# V1_01.net
KiCad netlist of a schematic drawn in EAGLE
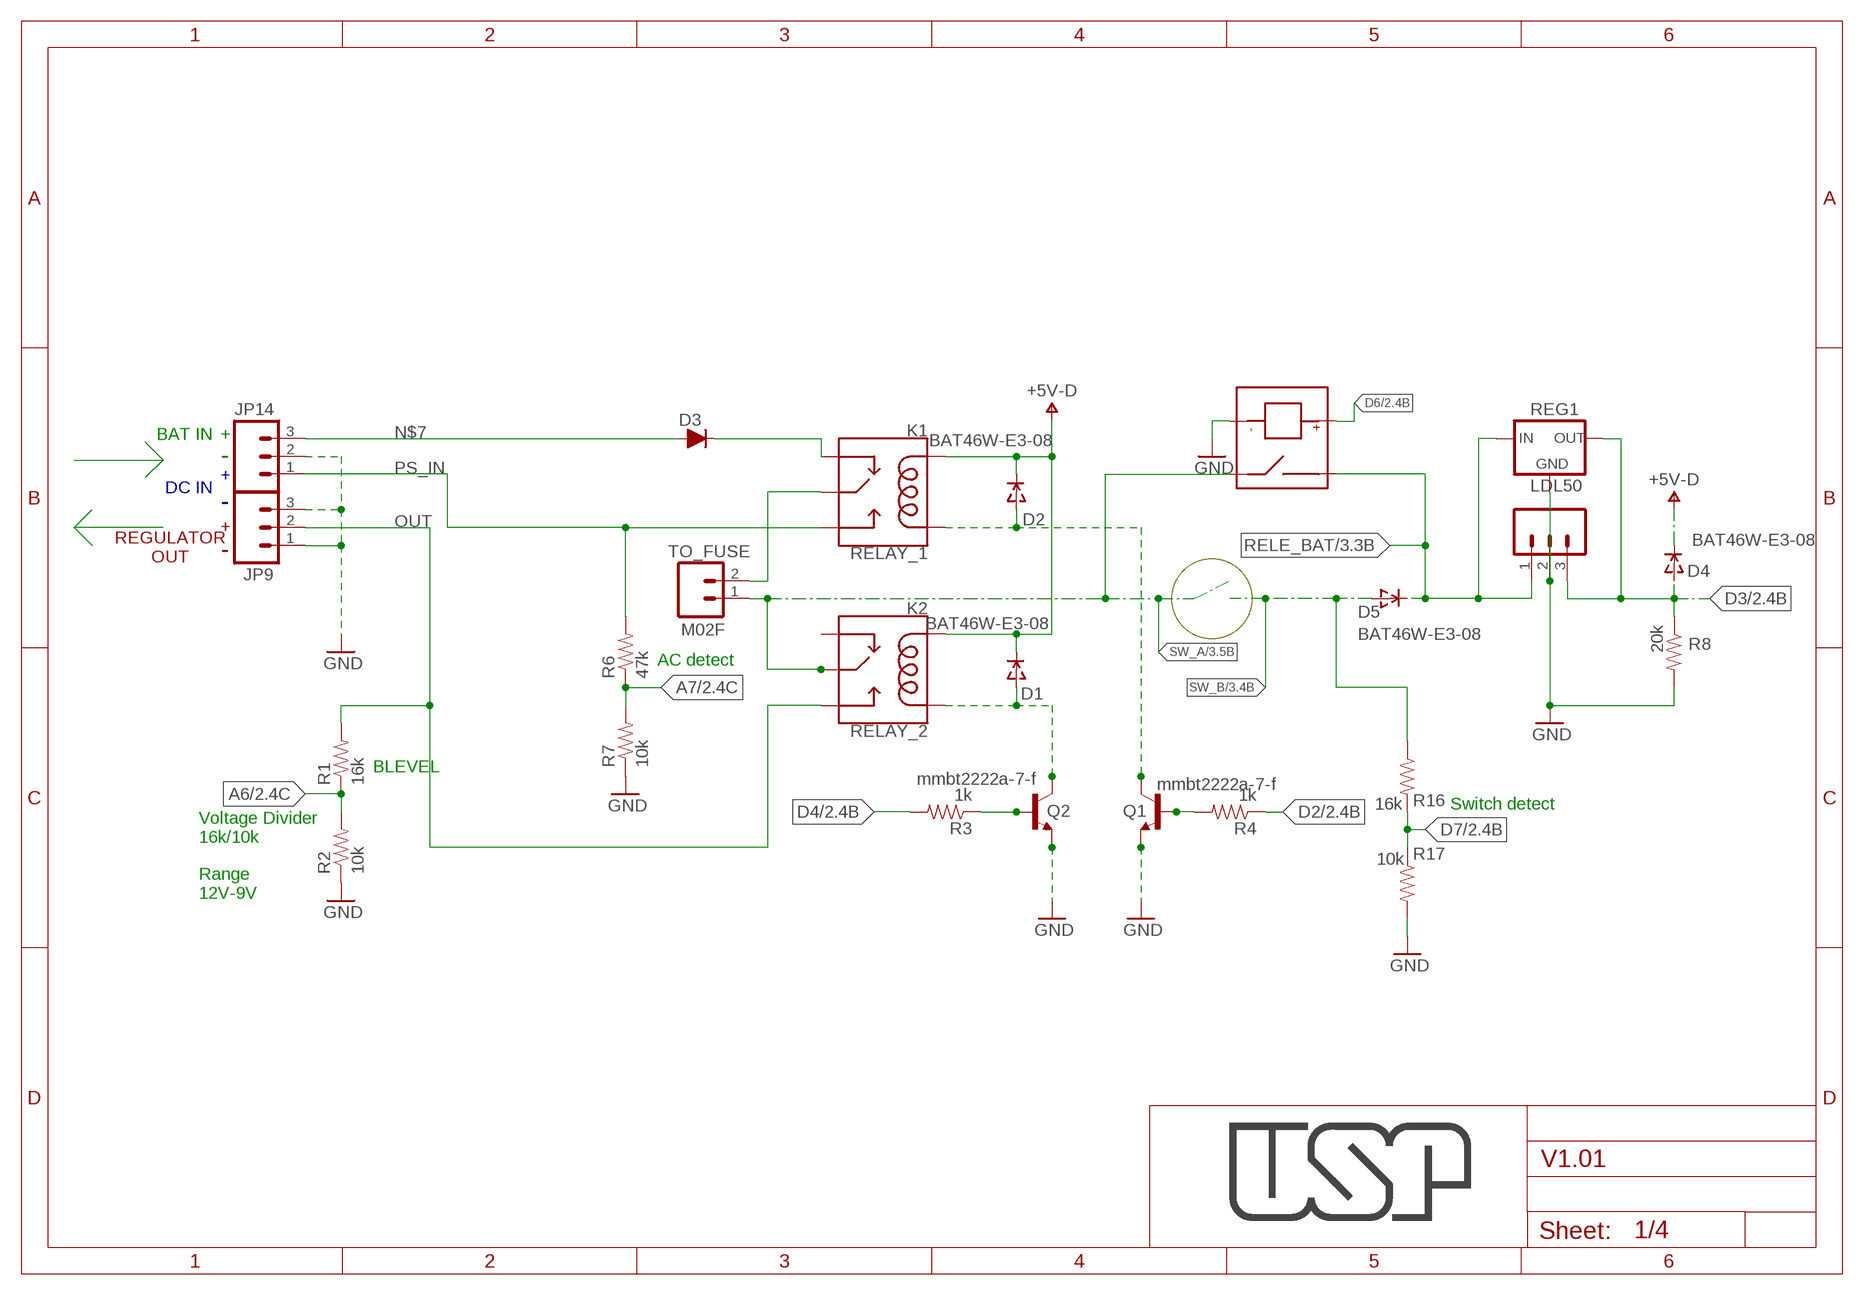
[diagram p0: schematic, sheet 1]
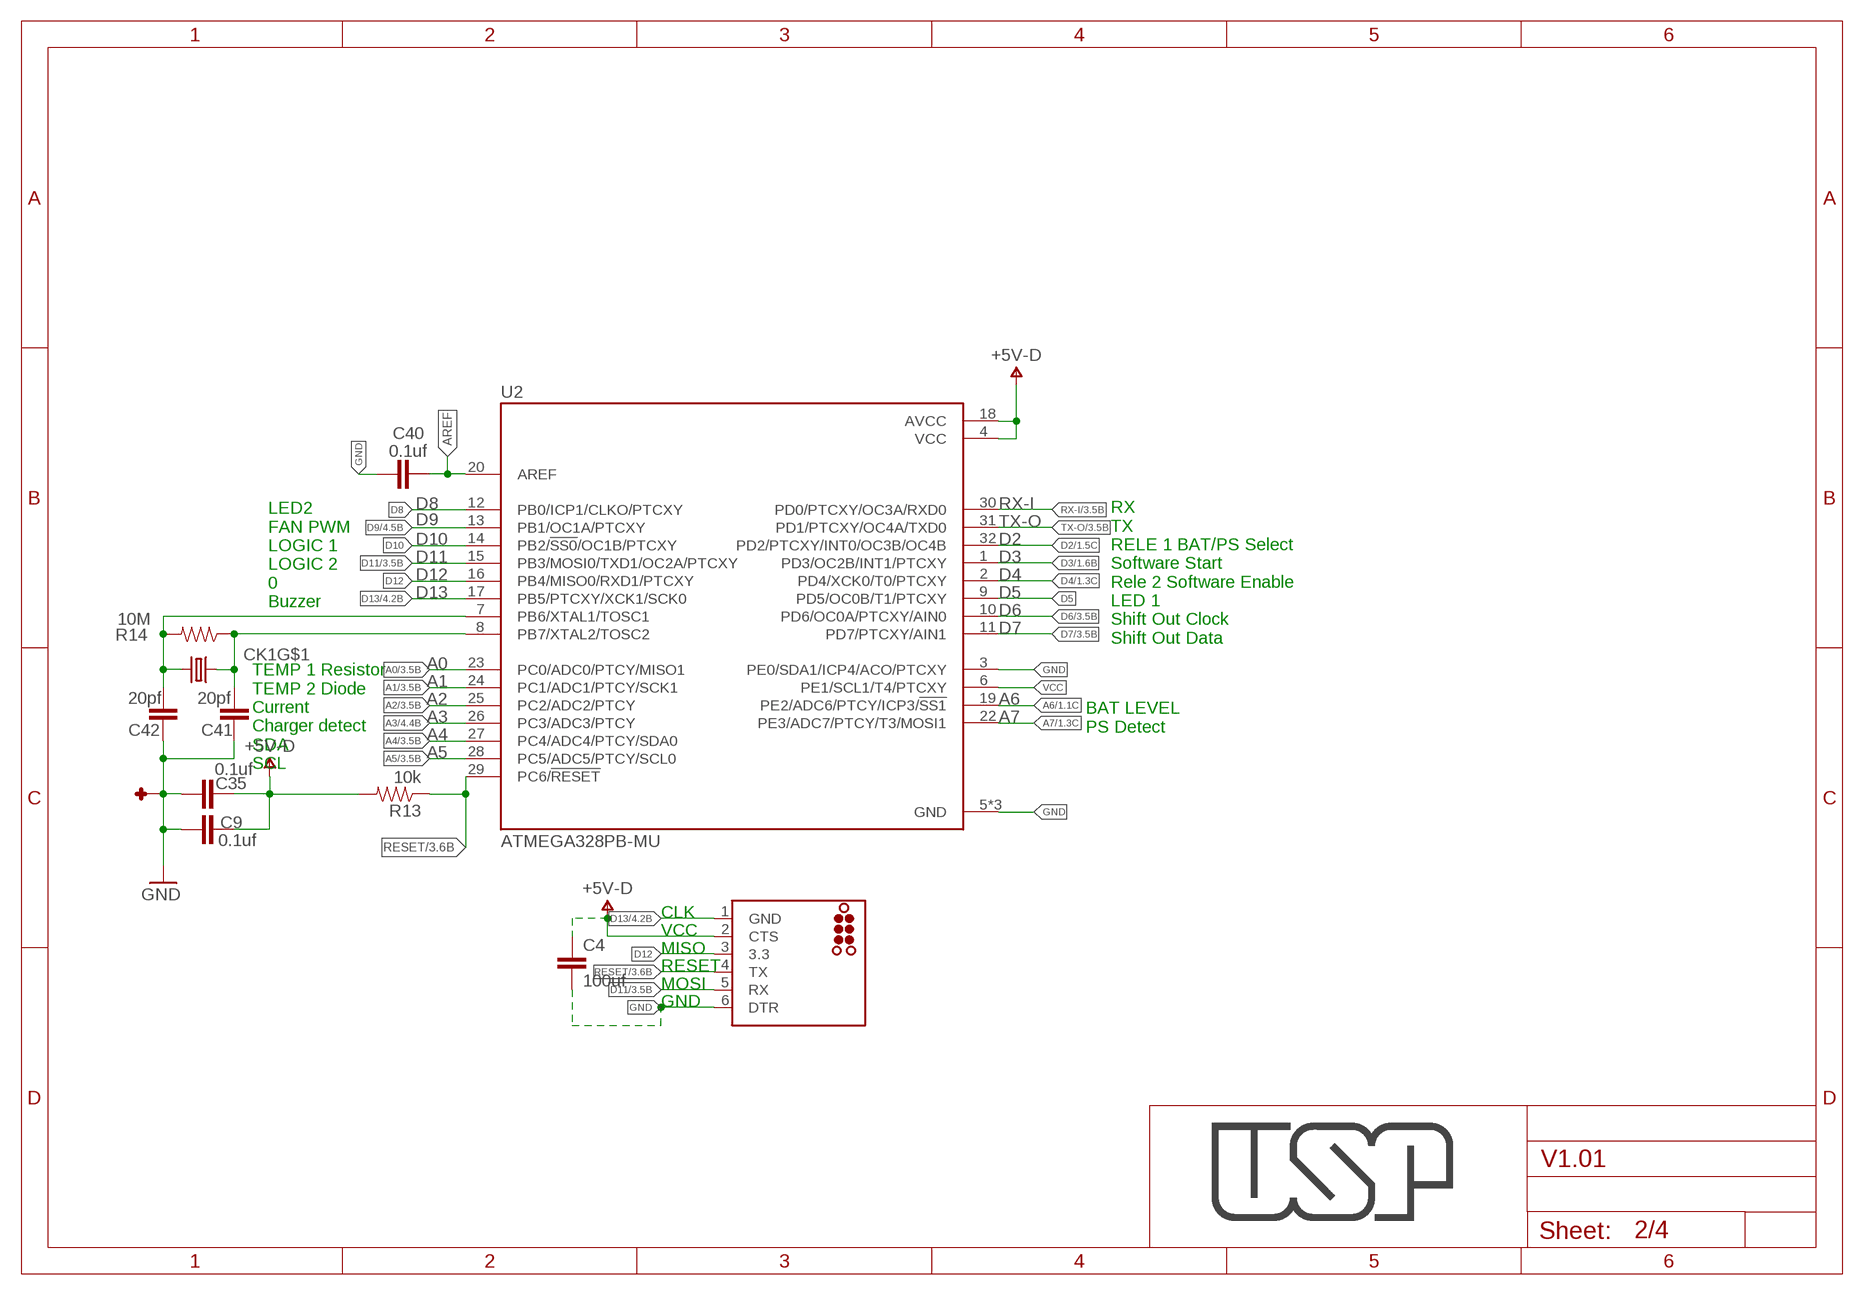
[diagram p1: schematic, sheet 2]
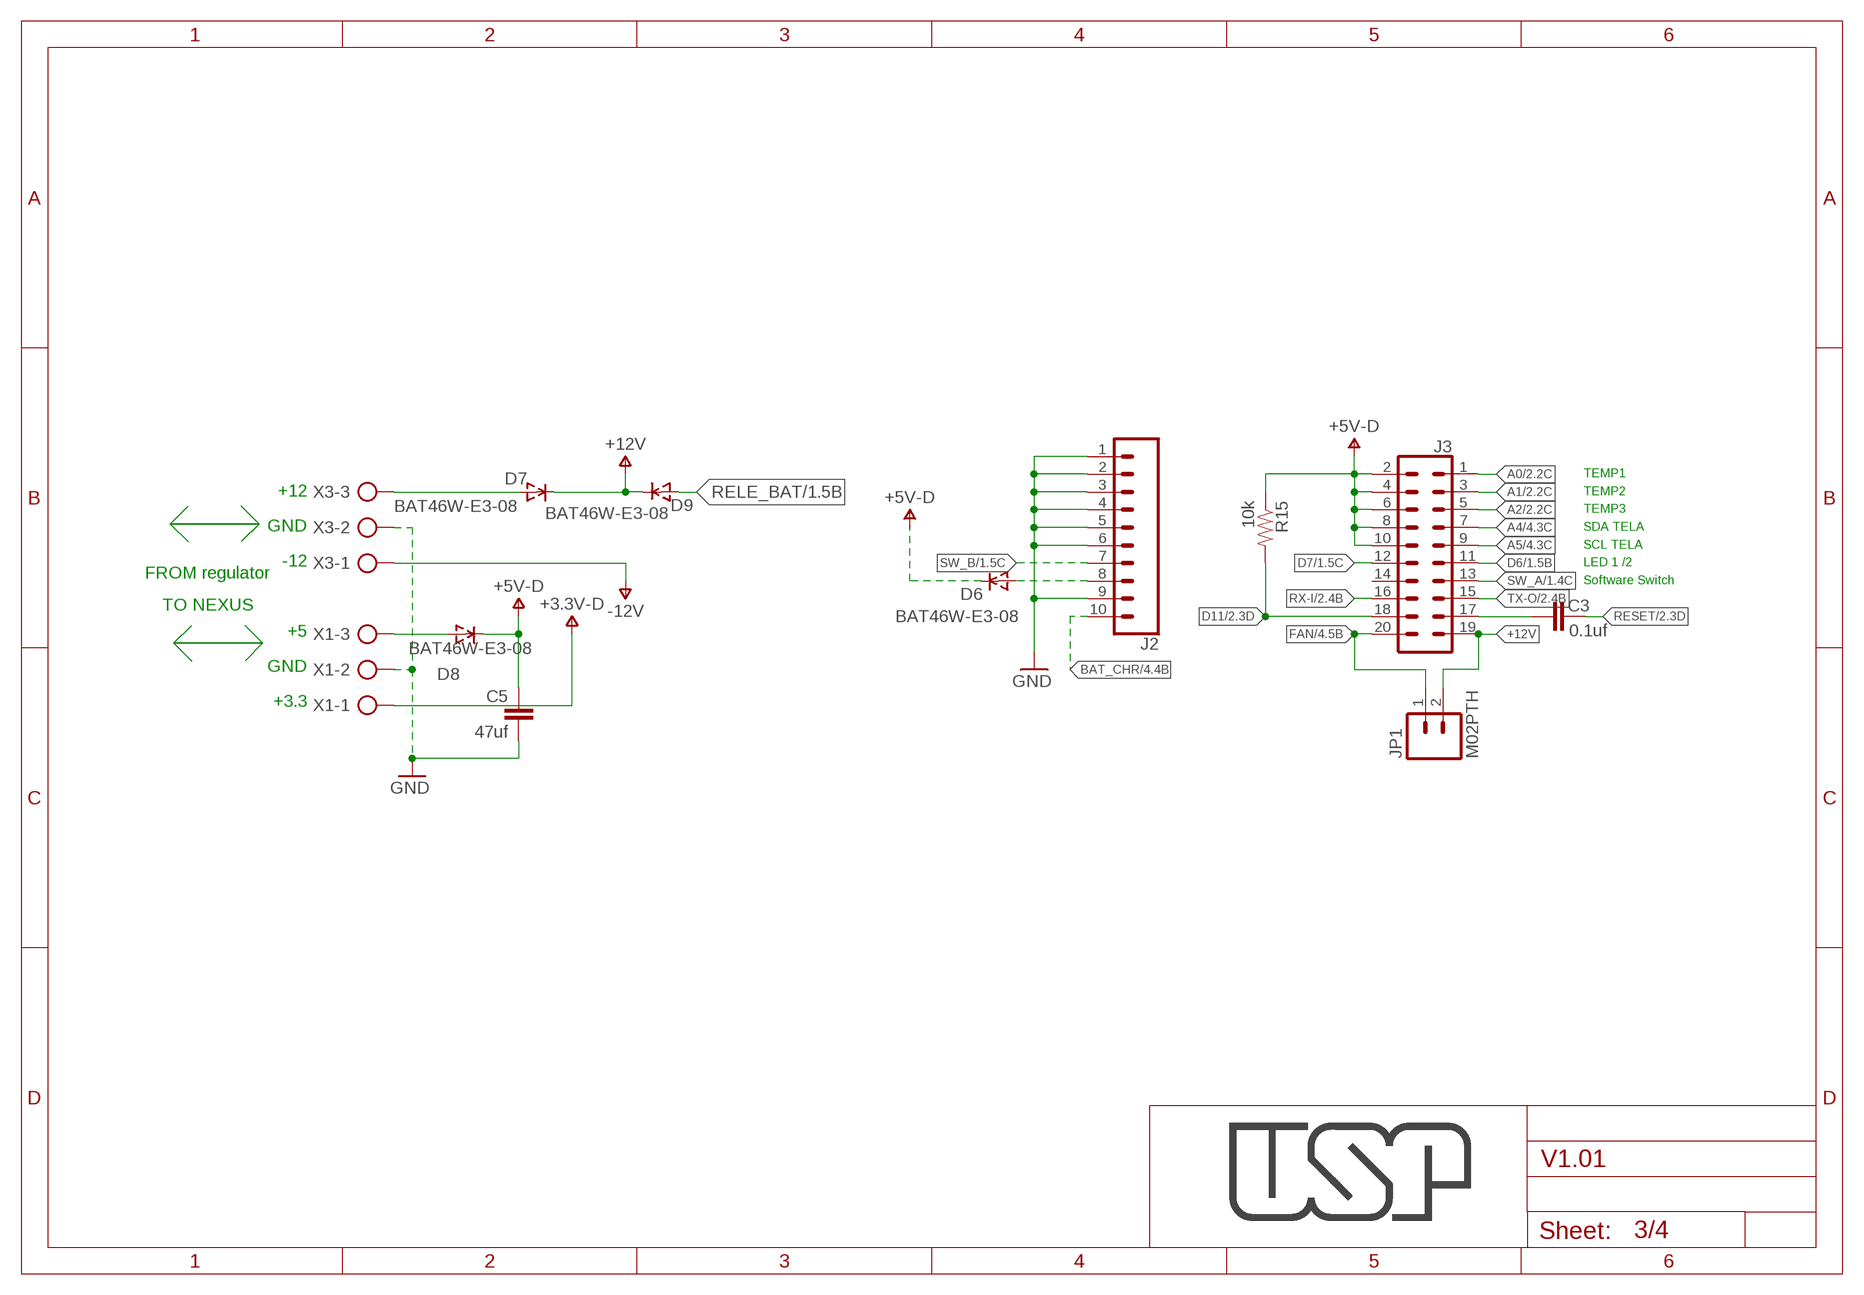
[diagram p2: schematic, sheet 3]
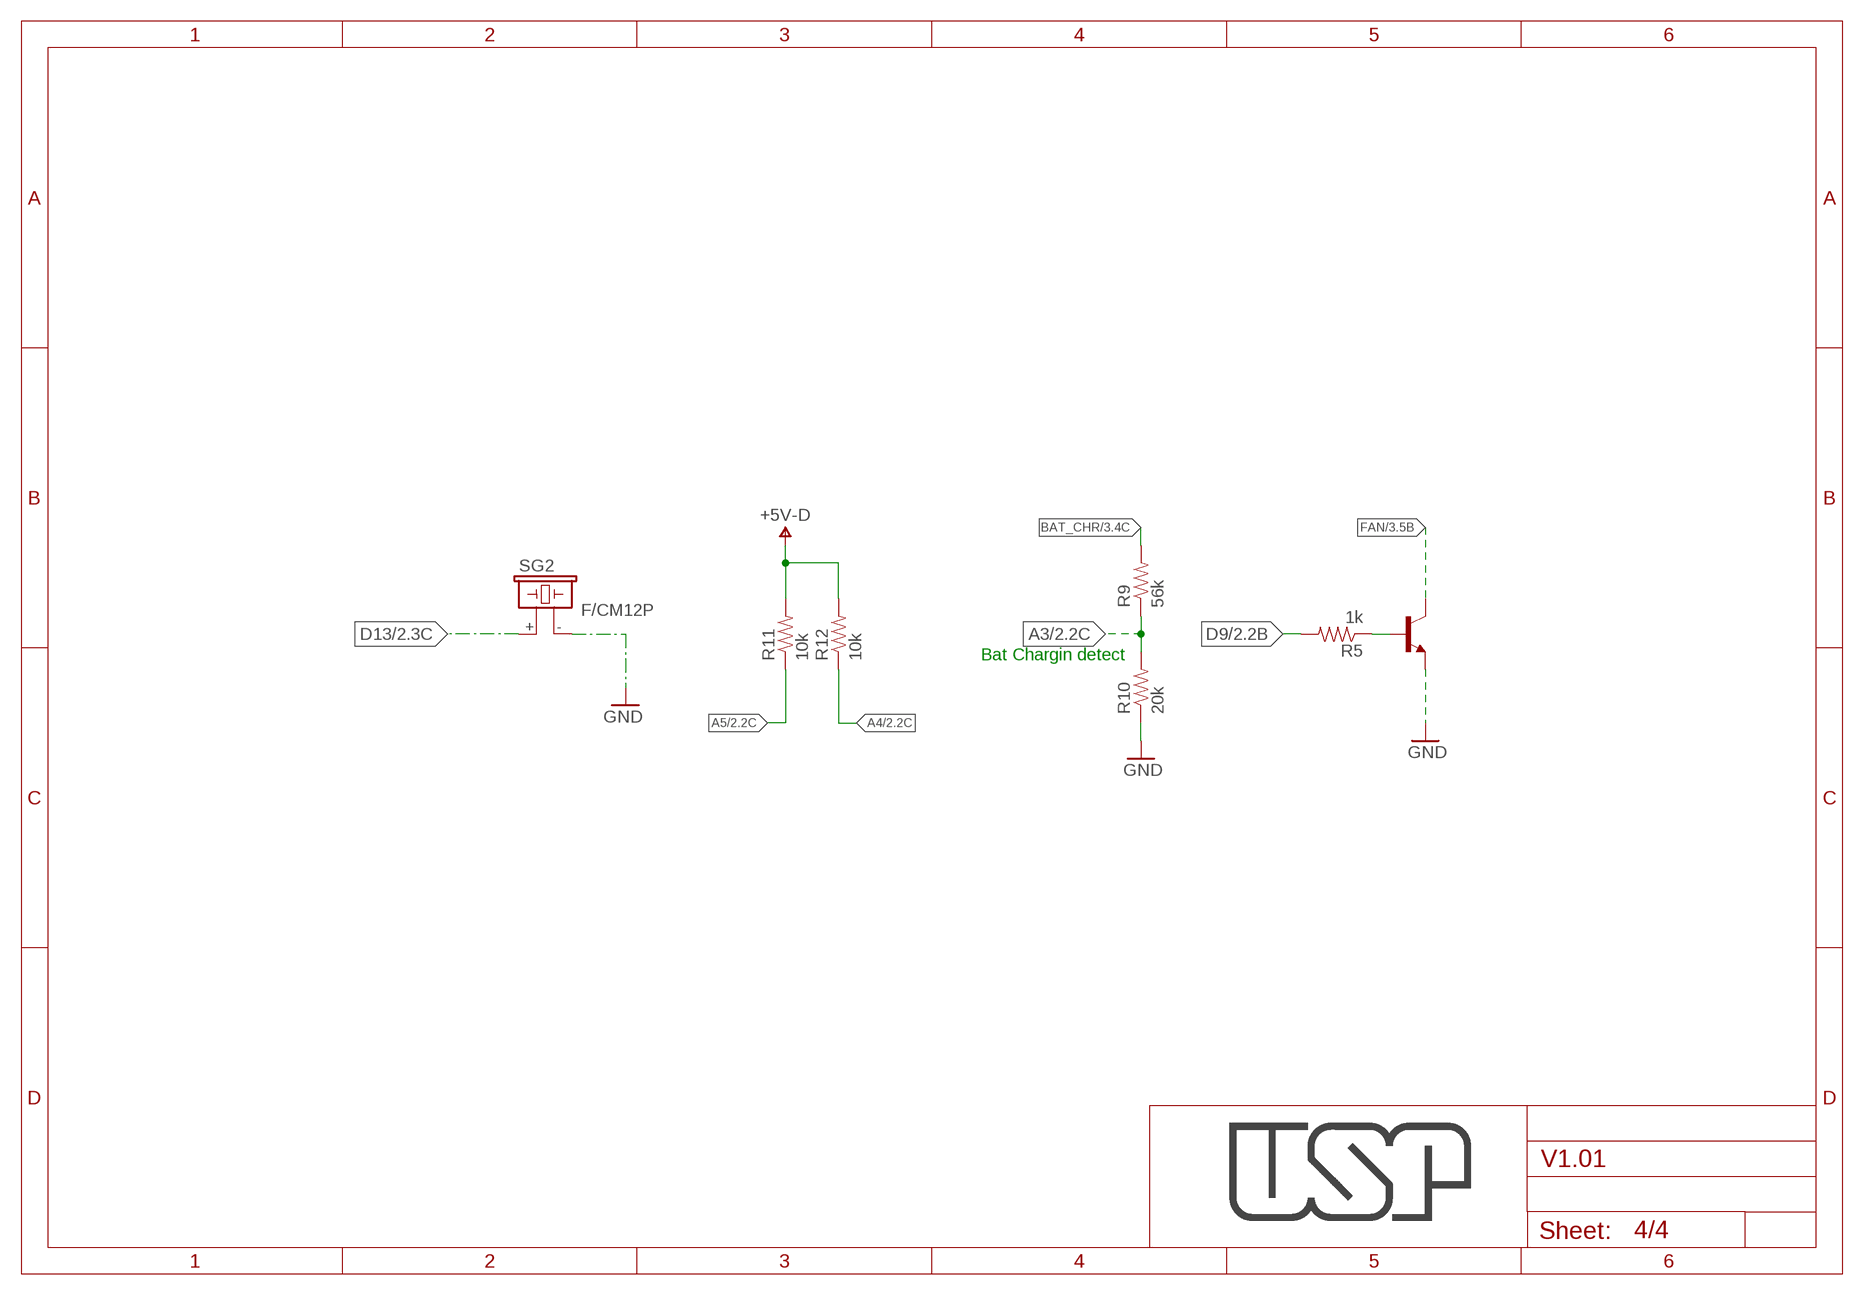
[diagram p3: schematic, sheet 4]

(export (version "E")
  (design (tool "Eeschema 10.0.6"))
  (components
    (comp (ref "C3")
      (value "0.1uf")
      (footprint "eagle-import:0402")
      (libsource (lib "eagle-import") (part "CAPACITOR-KIT-1VISHAY"))
    )
    (comp (ref "C5")
      (value "47uf")
      (footprint "eagle-import:1206")
      (libsource (lib "eagle-import") (part "CAPACITOR-KIT-11206"))
    )
    (comp (ref "D6")
      (value "BAT46W-E3-08")
      (footprint "eagle-import:SOD-123")
      (libsource (lib "eagle-import") (part "DIODE_1SOD-123"))
    )
    (comp (ref "D7")
      (value "BAT46W-E3-08")
      (footprint "eagle-import:SOD-123")
      (libsource (lib "eagle-import") (part "DIODE_1SOD-123"))
    )
    (comp (ref "D8")
      (value "BAT46W-E3-08")
      (footprint "eagle-import:SOD-123")
      (libsource (lib "eagle-import") (part "DIODE_1SOD-123"))
    )
    (comp (ref "D9")
      (value "BAT46W-E3-08")
      (footprint "eagle-import:SOD-123")
      (libsource (lib "eagle-import") (part "DIODE_1SOD-123"))
    )
    (comp (ref "J2")
      (value "CONN_10\"")
      (footprint "eagle-import:1X10")
      (libsource (lib "eagle-import") (part "CONN_10{dblquote}"))
    )
    (comp (ref "J3")
      (value "CONN_10X2")
      (footprint "eagle-import:2X10")
      (libsource (lib "eagle-import") (part "CONN_10X2"))
    )
    (comp (ref "JP1")
      (value "M02PTH")
      (footprint "eagle-import:1X02")
      (libsource (lib "eagle-import") (part "M02PTH"))
    )
    (comp (ref "R15")
      (value "10k")
      (footprint "eagle-import:0402")
      (libsource (lib "eagle-import") (part "RESISTORVISHAY"))
    )
    (comp (ref "X1")
      (value "AK500/3-H")
      (footprint "eagle-import:AK500_3-H")
      (libsource (lib "eagle-import") (part "AK500/3-H"))
    )
    (comp (ref "X3")
      (value "AK500/3-H")
      (footprint "eagle-import:AK500_3-H")
      (libsource (lib "eagle-import") (part "AK500/3-H"))
    )
    (comp (ref "C4")
      (value "100uf")
      (footprint "eagle-import:1206")
      (libsource (lib "eagle-import") (part "CAPACITOR-KIT-11206"))
    )
    (comp (ref "C9")
      (value "0.1uf")
      (footprint "eagle-import:0402")
      (libsource (lib "eagle-import") (part "CAPACITOR-KIT-1VISHAY"))
    )
    (comp (ref "C35")
      (value "0.1uf")
      (footprint "eagle-import:0402")
      (libsource (lib "eagle-import") (part "CAPACITOR-KIT-1VISHAY"))
    )
    (comp (ref "C40")
      (value "0.1uf")
      (footprint "eagle-import:0402")
      (libsource (lib "eagle-import") (part "CAPACITOR-KIT-1VISHAY"))
    )
    (comp (ref "C41")
      (value "20pf")
      (footprint "eagle-import:0402")
      (libsource (lib "eagle-import") (part "CAPACITOR-KIT-1VISHAY"))
    )
    (comp (ref "C42")
      (value "20pf")
      (footprint "eagle-import:0402")
      (libsource (lib "eagle-import") (part "CAPACITOR-KIT-1VISHAY"))
    )
    (comp (ref "CK1")
      (value "FA-238 16.0000MB-C3")
      (footprint "eagle-import:4-SMD@1")
      (libsource (lib "eagle-import") (part "CRYSTAL-4PAD"))
    )
    (comp (ref "J10")
      (value "DNP")
      (footprint "eagle-import:TC2030-MCP-NL")
      (libsource (lib "eagle-import") (part "FTDI-POGO-MCP-NL"))
    )
    (comp (ref "R13")
      (value "10k")
      (footprint "eagle-import:0402")
      (libsource (lib "eagle-import") (part "RESISTORVISHAY"))
    )
    (comp (ref "R14")
      (value "10M")
      (footprint "eagle-import:0402")
      (libsource (lib "eagle-import") (part "RESISTORVISHAY"))
    )
    (comp (ref "U2")
      (value "ATMEGA328PB-MU")
      (footprint "eagle-import:QFN50P500X500X90-33N")
      (fields (field (name "MF") "Microchip"))
      (libsource (lib "eagle-import") (part "ATMEGA328PB-MU"))
    )
    (comp (ref "Q5")
      (value "TRANSISTOR-NPN-BC337")
      (footprint "eagle-import:BC337")
      (libsource (lib "eagle-import") (part "TRANSISTOR-NPN-BC337"))
    )
    (comp (ref "R5")
      (value "1k")
      (footprint "eagle-import:0402")
      (libsource (lib "eagle-import") (part "RESISTORVISHAY"))
    )
    (comp (ref "R9")
      (value "56k")
      (footprint "eagle-import:0402")
      (libsource (lib "eagle-import") (part "RESISTORVISHAY"))
    )
    (comp (ref "R10")
      (value "20k")
      (footprint "eagle-import:0402")
      (libsource (lib "eagle-import") (part "RESISTORVISHAY"))
    )
    (comp (ref "R11")
      (value "10k")
      (footprint "eagle-import:0402")
      (libsource (lib "eagle-import") (part "RESISTORVISHAY"))
    )
    (comp (ref "R12")
      (value "10k")
      (footprint "eagle-import:0402")
      (libsource (lib "eagle-import") (part "RESISTORVISHAY"))
    )
    (comp (ref "SG2")
      (value "F/CM12P")
      (footprint "eagle-import:F_CM12P")
      (libsource (lib "eagle-import") (part "F/CM12P"))
    )
    (comp (ref "7805")
      (value "M03LOCK")
      (footprint "eagle-import:1X03_LOCK")
      (libsource (lib "eagle-import") (part "M03LOCK"))
    )
    (comp (ref "D1")
      (value "BAT46W-E3-08")
      (footprint "eagle-import:SOD-123")
      (libsource (lib "eagle-import") (part "DIODE_1SOD-123"))
    )
    (comp (ref "D2")
      (value "BAT46W-E3-08")
      (footprint "eagle-import:SOD-123")
      (libsource (lib "eagle-import") (part "DIODE_1SOD-123"))
    )
    (comp (ref "D3")
      (value "DIODEFR")
      (footprint "eagle-import:DIODE1.5A")
      (libsource (lib "eagle-import") (part "DIODEFR"))
    )
    (comp (ref "D4")
      (value "BAT46W-E3-08")
      (footprint "eagle-import:SOD-123")
      (libsource (lib "eagle-import") (part "DIODE_1SOD-123"))
    )
    (comp (ref "D5")
      (value "BAT46W-E3-08")
      (footprint "eagle-import:SOD-123")
      (libsource (lib "eagle-import") (part "DIODE_1SOD-123"))
    )
    (comp (ref "JP9")
      (value "M03")
      (footprint "eagle-import:AK500")
      (libsource (lib "eagle-import") (part "M03"))
    )
    (comp (ref "JP14")
      (value "M03")
      (footprint "eagle-import:AK500")
      (libsource (lib "eagle-import") (part "M03"))
    )
    (comp (ref "K1")
      (value "RELAY_1")
      (footprint "eagle-import:RELAY_G5LE")
      (libsource (lib "eagle-import") (part "RELAY-PACKA"))
    )
    (comp (ref "K2")
      (value "RELAY_2")
      (footprint "eagle-import:RELAY_G5LE")
      (libsource (lib "eagle-import") (part "RELAY-PACKA"))
    )
    (comp (ref "Q1")
      (value "mmbt2222a-7-f")
      (footprint "eagle-import:SOT23-3")
      (libsource (lib "eagle-import") (part "TRANSISTOR_NPNMPSA42"))
    )
    (comp (ref "Q2")
      (value "mmbt2222a-7-f")
      (footprint "eagle-import:SOT23-3")
      (libsource (lib "eagle-import") (part "TRANSISTOR_NPNMPSA42"))
    )
    (comp (ref "Q3")
      (value "TRANSISTOR-NPN-BC337")
      (footprint "eagle-import:BC337")
      (libsource (lib "eagle-import") (part "TRANSISTOR-NPN-BC337"))
    )
    (comp (ref "Q4")
      (value "TRANSISTOR-NPN-BC337")
      (footprint "eagle-import:BC337")
      (libsource (lib "eagle-import") (part "TRANSISTOR-NPN-BC337"))
    )
    (comp (ref "R1")
      (value "16k")
      (footprint "eagle-import:0402")
      (libsource (lib "eagle-import") (part "RESISTORVISHAY"))
    )
    (comp (ref "R2")
      (value "10k")
      (footprint "eagle-import:0402")
      (libsource (lib "eagle-import") (part "RESISTORVISHAY"))
    )
    (comp (ref "R3")
      (value "1k")
      (footprint "eagle-import:0402")
      (libsource (lib "eagle-import") (part "RESISTORVISHAY"))
    )
    (comp (ref "R4")
      (value "1k")
      (footprint "eagle-import:0402")
      (libsource (lib "eagle-import") (part "RESISTORVISHAY"))
    )
    (comp (ref "R6")
      (value "47k")
      (footprint "eagle-import:0402")
      (libsource (lib "eagle-import") (part "RESISTORVISHAY"))
    )
    (comp (ref "R7")
      (value "10k")
      (footprint "eagle-import:0402")
      (libsource (lib "eagle-import") (part "RESISTORVISHAY"))
    )
    (comp (ref "R8")
      (value "20k")
      (footprint "eagle-import:0402")
      (libsource (lib "eagle-import") (part "RESISTORVISHAY"))
    )
    (comp (ref "R16")
      (value "16k")
      (footprint "eagle-import:0402")
      (libsource (lib "eagle-import") (part "RESISTORVISHAY"))
    )
    (comp (ref "R17")
      (value "10k")
      (footprint "eagle-import:0402")
      (libsource (lib "eagle-import") (part "RESISTORVISHAY"))
    )
    (comp (ref "REG1")
      (value "LDL50")
      (footprint "eagle-import:SOT223")
      (libsource (lib "eagle-import") (part "REGULATOR_1117AMS117"))
    )
    (comp (ref "RL1")
      (value "RELAY_HE3621A0500")
      (footprint "eagle-import:HE3621A")
      (libsource (lib "eagle-import") (part "RELAY_HE3621A0500"))
    )
    (comp (ref "TO_FUSE")
      (value "M02F")
      (footprint "eagle-import:AK500M2")
      (libsource (lib "eagle-import") (part "M02F"))
    )
  )
  (nets
    (net (code "1") (name "+3.3V-D") (class "Default")
      (node (ref "X1") (pin "1") (pinfunction "KL_1") (pintype "passive"))
    )
    (net (code "2") (name "+5V-D") (class "Default")
      (node (ref "C35") (pin "P$2") (pinfunction "2_P$2") (pintype "passive"))
      (node (ref "C4") (pin "1") (pinfunction "1_1") (pintype "passive"))
      (node (ref "C5") (pin "1") (pinfunction "1_1") (pintype "passive"))
      (node (ref "C9") (pin "P$2") (pinfunction "2_P$2") (pintype "passive"))
      (node (ref "D1") (pin "C") (pinfunction "C_C") (pintype "passive"))
      (node (ref "D2") (pin "C") (pinfunction "C_C") (pintype "passive"))
      (node (ref "D4") (pin "C") (pinfunction "C_C") (pintype "passive"))
      (node (ref "D6") (pin "C") (pinfunction "C_C") (pintype "passive"))
      (node (ref "D8") (pin "C") (pinfunction "C_C") (pintype "passive"))
      (node (ref "J10") (pin "2") (pinfunction "CTS_2") (pintype "power_in"))
      (node (ref "J3") (pin "10") (pinfunction "10_10") (pintype "passive"))
      (node (ref "J3") (pin "2") (pinfunction "2_2") (pintype "passive"))
      (node (ref "J3") (pin "4") (pinfunction "4_4") (pintype "passive"))
      (node (ref "J3") (pin "6") (pinfunction "6_6") (pintype "passive"))
      (node (ref "J3") (pin "8") (pinfunction "8_8") (pintype "passive"))
      (node (ref "K1") (pin "2") (pinfunction "COIL1_2") (pintype "bidirectional"))
      (node (ref "K2") (pin "2") (pinfunction "COIL1_2") (pintype "bidirectional"))
      (node (ref "R11") (pin "P$2") (pinfunction "2_P$2") (pintype "passive"))
      (node (ref "R12") (pin "P$2") (pinfunction "2_P$2") (pintype "passive"))
      (node (ref "R13") (pin "P$2") (pinfunction "2_P$2") (pintype "passive"))
      (node (ref "R15") (pin "P$1") (pinfunction "1_P$1") (pintype "passive"))
      (node (ref "U2") (pin "18") (pinfunction "AVCC_18") (pintype "power_in"))
      (node (ref "U2") (pin "4") (pinfunction "VCC_4") (pintype "power_in"))
    )
    (net (code "3") (name "+12V") (class "Default")
      (node (ref "D7") (pin "C") (pinfunction "C_C") (pintype "passive"))
      (node (ref "D9") (pin "C") (pinfunction "C_C") (pintype "passive"))
      (node (ref "J3") (pin "19") (pinfunction "19_19") (pintype "passive"))
      (node (ref "JP1") (pin "2") (pinfunction "2_2") (pintype "passive"))
    )
    (net (code "4") (name "-12V") (class "Default")
      (node (ref "X3") (pin "1") (pinfunction "KL_1") (pintype "passive"))
    )
    (net (code "5") (name "A0") (class "Default")
      (node (ref "J3") (pin "1") (pinfunction "1_1") (pintype "passive"))
      (node (ref "U2") (pin "23") (pinfunction "PC0/ADC0/PTCY/MISO1_23") (pintype "bidirectional"))
    )
    (net (code "6") (name "A1") (class "Default")
      (node (ref "J3") (pin "3") (pinfunction "3_3") (pintype "passive"))
      (node (ref "U2") (pin "24") (pinfunction "PC1/ADC1/PTCY/SCK1_24") (pintype "bidirectional"))
    )
    (net (code "7") (name "A2") (class "Default")
      (node (ref "J3") (pin "5") (pinfunction "5_5") (pintype "passive"))
      (node (ref "U2") (pin "25") (pinfunction "PC2/ADC2/PTCY_25") (pintype "bidirectional"))
    )
    (net (code "8") (name "A3") (class "Default")
      (node (ref "R10") (pin "P$2") (pinfunction "2_P$2") (pintype "passive"))
      (node (ref "R9") (pin "P$1") (pinfunction "1_P$1") (pintype "passive"))
      (node (ref "U2") (pin "26") (pinfunction "PC3/ADC3/PTCY_26") (pintype "bidirectional"))
    )
    (net (code "9") (name "A4") (class "Default")
      (node (ref "J3") (pin "7") (pinfunction "7_7") (pintype "passive"))
      (node (ref "R12") (pin "P$1") (pinfunction "1_P$1") (pintype "passive"))
      (node (ref "U2") (pin "27") (pinfunction "PC4/ADC4/PTCY/SDA0_27") (pintype "bidirectional"))
    )
    (net (code "10") (name "A5") (class "Default")
      (node (ref "J3") (pin "9") (pinfunction "9_9") (pintype "passive"))
      (node (ref "R11") (pin "P$1") (pinfunction "1_P$1") (pintype "passive"))
      (node (ref "U2") (pin "28") (pinfunction "PC5/ADC5/PTCY/SCL0_28") (pintype "bidirectional"))
    )
    (net (code "11") (name "A6") (class "Default")
      (node (ref "R1") (pin "P$1") (pinfunction "1_P$1") (pintype "passive"))
      (node (ref "R2") (pin "P$2") (pinfunction "2_P$2") (pintype "passive"))
      (node (ref "U2") (pin "19") (pinfunction "PE2/ADC6/PTCY/ICP3/~{SS1}_19") (pintype "bidirectional"))
    )
    (net (code "12") (name "A7") (class "Default")
      (node (ref "R6") (pin "P$1") (pinfunction "1_P$1") (pintype "passive"))
      (node (ref "R7") (pin "P$2") (pinfunction "2_P$2") (pintype "passive"))
      (node (ref "U2") (pin "22") (pinfunction "PE3/ADC7/PTCY/T3/MOSI1_22") (pintype "bidirectional"))
    )
    (net (code "13") (name "AREF") (class "Default")
      (node (ref "C40") (pin "P$1") (pinfunction "1_P$1") (pintype "passive"))
      (node (ref "U2") (pin "20") (pinfunction "AREF_20") (pintype "input"))
    )
    (net (code "14") (name "BAT_CHR") (class "Default")
      (node (ref "J2") (pin "10") (pinfunction "10_10") (pintype "passive"))
      (node (ref "R9") (pin "P$2") (pinfunction "2_P$2") (pintype "passive"))
    )
    (net (code "15") (name "D2") (class "Default")
      (node (ref "R4") (pin "P$1") (pinfunction "1_P$1") (pintype "passive"))
      (node (ref "U2") (pin "32") (pinfunction "PD2/PTCXY/INT0/OC3B/OC4B_32") (pintype "bidirectional"))
    )
    (net (code "16") (name "D3") (class "Default")
      (node (ref "7805") (pin "3") (pinfunction "3_3") (pintype "passive"))
      (node (ref "D4") (pin "A") (pinfunction "A_A") (pintype "passive"))
      (node (ref "R8") (pin "P$1") (pinfunction "1_P$1") (pintype "passive"))
      (node (ref "REG1") (pin "2") (pinfunction "OUT_2") (pintype "output"))
      (node (ref "REG1") (pin "4") (pinfunction "OUT_4") (pintype "output"))
      (node (ref "U2") (pin "1") (pinfunction "PD3/OC2B/INT1/PTCXY_1") (pintype "bidirectional"))
    )
    (net (code "17") (name "D4") (class "Default")
      (node (ref "R3") (pin "P$2") (pinfunction "2_P$2") (pintype "passive"))
      (node (ref "U2") (pin "2") (pinfunction "PD4/XCK0/T0/PTCXY_2") (pintype "bidirectional"))
    )
    (net (code "18") (name "D5") (class "Default")
      (node (ref "U2") (pin "9") (pinfunction "PD5/OC0B/T1/PTCXY_9") (pintype "bidirectional"))
    )
    (net (code "19") (name "D6") (class "Default")
      (node (ref "J3") (pin "11") (pinfunction "11_11") (pintype "passive"))
      (node (ref "RL1") (pin "P2") (pinfunction "P2_P2") (pintype "bidirectional"))
      (node (ref "U2") (pin "10") (pinfunction "PD6/OC0A/PTCXY/AIN0_10") (pintype "bidirectional"))
    )
    (net (code "20") (name "D7") (class "Default")
      (node (ref "J3") (pin "12") (pinfunction "12_12") (pintype "passive"))
      (node (ref "R16") (pin "P$2") (pinfunction "2_P$2") (pintype "passive"))
      (node (ref "R17") (pin "P$1") (pinfunction "1_P$1") (pintype "passive"))
      (node (ref "U2") (pin "11") (pinfunction "PD7/PTCXY/AIN1_11") (pintype "bidirectional"))
    )
    (net (code "21") (name "D8") (class "Default")
      (node (ref "U2") (pin "12") (pinfunction "PB0/ICP1/CLKO/PTCXY_12") (pintype "bidirectional"))
    )
    (net (code "22") (name "D9") (class "Default")
      (node (ref "R5") (pin "P$2") (pinfunction "2_P$2") (pintype "passive"))
      (node (ref "U2") (pin "13") (pinfunction "PB1/OC1A/PTCXY_13") (pintype "bidirectional"))
    )
    (net (code "23") (name "D10") (class "Default")
      (node (ref "U2") (pin "14") (pinfunction "PB2/~{SS0}/OC1B/PTCXY_14") (pintype "bidirectional"))
    )
    (net (code "24") (name "D11") (class "Default")
      (node (ref "J10") (pin "5") (pinfunction "RX_5") (pintype "output"))
      (node (ref "J3") (pin "18") (pinfunction "18_18") (pintype "passive"))
      (node (ref "R15") (pin "P$2") (pinfunction "2_P$2") (pintype "passive"))
      (node (ref "U2") (pin "15") (pinfunction "PB3/MOSI0/TXD1/OC2A/PTCXY_15") (pintype "bidirectional"))
    )
    (net (code "25") (name "D12") (class "Default")
      (node (ref "J10") (pin "3") (pinfunction "3.3_3") (pintype "power_in"))
      (node (ref "U2") (pin "16") (pinfunction "PB4/MISO0/RXD1/PTCXY_16") (pintype "bidirectional"))
    )
    (net (code "26") (name "D13") (class "Default")
      (node (ref "J10") (pin "1") (pinfunction "GND_1") (pintype "passive"))
      (node (ref "SG2") (pin "+") (pinfunction "1_+") (pintype "passive"))
      (node (ref "U2") (pin "17") (pinfunction "PB5/PTCXY/XCK1/SCK0_17") (pintype "bidirectional"))
    )
    (net (code "27") (name "FAN") (class "Default")
      (node (ref "J3") (pin "20") (pinfunction "20_20") (pintype "passive"))
      (node (ref "JP1") (pin "1") (pinfunction "1_1") (pintype "passive"))
      (node (ref "Q5") (pin "3") (pinfunction "C_3") (pintype "passive"))
    )
    (net (code "28") (name "GND") (class "Default")
      (node (ref "7805") (pin "2") (pinfunction "2_2") (pintype "passive"))
      (node (ref "C35") (pin "P$1") (pinfunction "1_P$1") (pintype "passive"))
      (node (ref "C4") (pin "2") (pinfunction "2_2") (pintype "passive"))
      (node (ref "C40") (pin "P$2") (pinfunction "2_P$2") (pintype "passive"))
      (node (ref "C41") (pin "P$2") (pinfunction "2_P$2") (pintype "passive"))
      (node (ref "C42") (pin "P$2") (pinfunction "2_P$2") (pintype "passive"))
      (node (ref "C5") (pin "2") (pinfunction "2_2") (pintype "passive"))
      (node (ref "C9") (pin "P$1") (pinfunction "1_P$1") (pintype "passive"))
      (node (ref "CK1") (pin "GND1") (pinfunction "1_GND1") (pintype "passive"))
      (node (ref "CK1") (pin "GND2") (pinfunction "1_GND2") (pintype "passive"))
      (node (ref "J10") (pin "6") (pinfunction "DTR_6") (pintype "bidirectional"))
      (node (ref "J2") (pin "1") (pinfunction "1_1") (pintype "passive"))
      (node (ref "J2") (pin "2") (pinfunction "2_2") (pintype "passive"))
      (node (ref "J2") (pin "3") (pinfunction "3_3") (pintype "passive"))
      (node (ref "J2") (pin "4") (pinfunction "4_4") (pintype "passive"))
      (node (ref "J2") (pin "5") (pinfunction "5_5") (pintype "passive"))
      (node (ref "J2") (pin "6") (pinfunction "6_6") (pintype "passive"))
      (node (ref "J2") (pin "9") (pinfunction "9_9") (pintype "passive"))
      (node (ref "JP14") (pin "2") (pinfunction "2_2") (pintype "passive"))
      (node (ref "JP9") (pin "1") (pinfunction "1_1") (pintype "passive"))
      (node (ref "JP9") (pin "3") (pinfunction "3_3") (pintype "passive"))
      (node (ref "Q1") (pin "2") (pinfunction "E_2") (pintype "passive"))
      (node (ref "Q2") (pin "2") (pinfunction "E_2") (pintype "passive"))
      (node (ref "Q3") (pin "1") (pinfunction "E_1") (pintype "passive"))
      (node (ref "Q4") (pin "1") (pinfunction "E_1") (pintype "passive"))
      (node (ref "Q5") (pin "1") (pinfunction "E_1") (pintype "passive"))
      (node (ref "R10") (pin "P$1") (pinfunction "1_P$1") (pintype "passive"))
      (node (ref "R17") (pin "P$2") (pinfunction "2_P$2") (pintype "passive"))
      (node (ref "R2") (pin "P$1") (pinfunction "1_P$1") (pintype "passive"))
      (node (ref "R7") (pin "P$1") (pinfunction "1_P$1") (pintype "passive"))
      (node (ref "R8") (pin "P$2") (pinfunction "2_P$2") (pintype "passive"))
      (node (ref "REG1") (pin "1") (pinfunction "GND_1") (pintype "input"))
      (node (ref "RL1") (pin "P3") (pinfunction "P3_P3") (pintype "bidirectional"))
      (node (ref "SG2") (pin "-") (pinfunction "2_-") (pintype "passive"))
      (node (ref "U2") (pin "21") (pinfunction "GND_21") (pintype "power_in"))
      (node (ref "U2") (pin "3") (pinfunction "PE0/SDA1/ICP4/ACO/PTCXY_3") (pintype "bidirectional"))
      (node (ref "U2") (pin "33") (pinfunction "GND_33") (pintype "power_in"))
      (node (ref "U2") (pin "5") (pinfunction "GND_5") (pintype "power_in"))
      (node (ref "X1") (pin "2") (pinfunction "KL_2") (pintype "passive"))
      (node (ref "X3") (pin "2") (pinfunction "KL_2") (pintype "passive"))
    )
    (net (code "29") (name "N$7") (class "Default")
      (node (ref "D3") (pin "A") (pinfunction "A_A") (pintype "passive"))
      (node (ref "JP14") (pin "3") (pinfunction "3_3") (pintype "passive"))
    )
    (net (code "30") (name "Net-(C3-1)") (class "Default")
      (node (ref "C3") (pin "P$1") (pinfunction "1_P$1") (pintype "passive"))
      (node (ref "J3") (pin "17") (pinfunction "17_17") (pintype "passive"))
    )
    (net (code "31") (name "Net-(C41-1)") (class "Default")
      (node (ref "C41") (pin "P$1") (pinfunction "1_P$1") (pintype "passive"))
      (node (ref "CK1") (pin "P1") (pinfunction "1_P1") (pintype "passive"))
      (node (ref "R14") (pin "P$1") (pinfunction "1_P$1") (pintype "passive"))
      (node (ref "U2") (pin "8") (pinfunction "PB7/XTAL2/TOSC2_8") (pintype "bidirectional"))
    )
    (net (code "32") (name "Net-(C42-1)") (class "Default")
      (node (ref "C42") (pin "P$1") (pinfunction "1_P$1") (pintype "passive"))
      (node (ref "CK1") (pin "P3") (pinfunction "2_P3") (pintype "passive"))
      (node (ref "R14") (pin "P$2") (pinfunction "2_P$2") (pintype "passive"))
      (node (ref "U2") (pin "7") (pinfunction "PB6/XTAL1/TOSC1_7") (pintype "bidirectional"))
    )
    (net (code "33") (name "Net-(D6-PadA)") (class "Default")
      (node (ref "D6") (pin "A") (pinfunction "A_A") (pintype "passive"))
      (node (ref "J2") (pin "8") (pinfunction "8_8") (pintype "passive"))
    )
    (net (code "34") (name "Net-(K1-COIL2)") (class "Default")
      (node (ref "D2") (pin "A") (pinfunction "A_A") (pintype "passive"))
      (node (ref "K1") (pin "5") (pinfunction "COIL2_5") (pintype "bidirectional"))
      (node (ref "Q1") (pin "3") (pinfunction "C_3") (pintype "passive"))
      (node (ref "Q4") (pin "3") (pinfunction "C_3") (pintype "passive"))
    )
    (net (code "35") (name "Net-(K1-MAIN)") (class "Default")
      (node (ref "K1") (pin "1") (pinfunction "MAIN_1") (pintype "bidirectional"))
      (node (ref "TO_FUSE") (pin "2") (pinfunction "2_2") (pintype "passive"))
    )
    (net (code "36") (name "Net-(K1-NC)") (class "Default")
      (node (ref "D3") (pin "C") (pinfunction "C_C") (pintype "passive"))
      (node (ref "K1") (pin "4") (pinfunction "NC_4") (pintype "bidirectional"))
    )
    (net (code "37") (name "Net-(K2-COIL2)") (class "Default")
      (node (ref "D1") (pin "A") (pinfunction "A_A") (pintype "passive"))
      (node (ref "K2") (pin "5") (pinfunction "COIL2_5") (pintype "bidirectional"))
      (node (ref "Q2") (pin "3") (pinfunction "C_3") (pintype "passive"))
      (node (ref "Q3") (pin "3") (pinfunction "C_3") (pintype "passive"))
    )
    (net (code "38") (name "Net-(Q1-B)") (class "Default")
      (node (ref "Q1") (pin "1") (pinfunction "B_1") (pintype "passive"))
      (node (ref "Q4") (pin "2") (pinfunction "B_2") (pintype "passive"))
      (node (ref "R4") (pin "P$2") (pinfunction "2_P$2") (pintype "passive"))
    )
    (net (code "39") (name "Net-(Q2-B)") (class "Default")
      (node (ref "Q2") (pin "1") (pinfunction "B_1") (pintype "passive"))
      (node (ref "Q3") (pin "2") (pinfunction "B_2") (pintype "passive"))
      (node (ref "R3") (pin "P$1") (pinfunction "1_P$1") (pintype "passive"))
    )
    (net (code "40") (name "Net-(Q5-B)") (class "Default")
      (node (ref "Q5") (pin "2") (pinfunction "B_2") (pintype "passive"))
      (node (ref "R5") (pin "P$1") (pinfunction "1_P$1") (pintype "passive"))
    )
    (net (code "41") (name "Net-(X1C-KL)") (class "Default")
      (node (ref "D8") (pin "A") (pinfunction "A_A") (pintype "passive"))
      (node (ref "X1") (pin "3") (pinfunction "KL_3") (pintype "passive"))
    )
    (net (code "42") (name "Net-(X3C-KL)") (class "Default")
      (node (ref "D7") (pin "A") (pinfunction "A_A") (pintype "passive"))
      (node (ref "X3") (pin "3") (pinfunction "KL_3") (pintype "passive"))
    )
    (net (code "43") (name "OUT") (class "Default")
      (node (ref "JP9") (pin "2") (pinfunction "2_2") (pintype "passive"))
      (node (ref "K2") (pin "3") (pinfunction "NO_3") (pintype "bidirectional"))
      (node (ref "R1") (pin "P$2") (pinfunction "2_P$2") (pintype "passive"))
    )
    (net (code "44") (name "PS_IN") (class "Default")
      (node (ref "JP14") (pin "1") (pinfunction "1_1") (pintype "passive"))
      (node (ref "K1") (pin "3") (pinfunction "NO_3") (pintype "bidirectional"))
      (node (ref "R6") (pin "P$2") (pinfunction "2_P$2") (pintype "passive"))
    )
    (net (code "45") (name "RELE_BAT") (class "Default")
      (node (ref "7805") (pin "1") (pinfunction "1_1") (pintype "passive"))
      (node (ref "D5") (pin "C") (pinfunction "C_C") (pintype "passive"))
      (node (ref "D9") (pin "A") (pinfunction "A_A") (pintype "passive"))
      (node (ref "REG1") (pin "3") (pinfunction "IN_3") (pintype "input"))
      (node (ref "RL1") (pin "P1") (pinfunction "P1_P1") (pintype "bidirectional"))
    )
    (net (code "46") (name "RESET") (class "Default")
      (node (ref "C3") (pin "P$2") (pinfunction "2_P$2") (pintype "passive"))
      (node (ref "J10") (pin "4") (pinfunction "TX_4") (pintype "bidirectional"))
      (node (ref "R13") (pin "P$1") (pinfunction "1_P$1") (pintype "passive"))
      (node (ref "U2") (pin "29") (pinfunction "PC6/~{RESET}_29") (pintype "bidirectional"))
    )
    (net (code "47") (name "RX-I") (class "Default")
      (node (ref "J3") (pin "16") (pinfunction "16_16") (pintype "passive"))
      (node (ref "U2") (pin "30") (pinfunction "PD0/PTCXY/OC3A/RXD0_30") (pintype "bidirectional"))
    )
    (net (code "48") (name "SW_A") (class "Default")
      (node (ref "J3") (pin "13") (pinfunction "13_13") (pintype "passive"))
      (node (ref "K2") (pin "1") (pinfunction "MAIN_1") (pintype "bidirectional"))
      (node (ref "RL1") (pin "P4") (pinfunction "P4_P4") (pintype "bidirectional"))
      (node (ref "TO_FUSE") (pin "1") (pinfunction "1_1") (pintype "passive"))
    )
    (net (code "49") (name "SW_B") (class "Default")
      (node (ref "D5") (pin "A") (pinfunction "A_A") (pintype "passive"))
      (node (ref "J2") (pin "7") (pinfunction "7_7") (pintype "passive"))
      (node (ref "R16") (pin "P$1") (pinfunction "1_P$1") (pintype "passive"))
    )
    (net (code "50") (name "TX-O") (class "Default")
      (node (ref "J3") (pin "15") (pinfunction "15_15") (pintype "passive"))
      (node (ref "U2") (pin "31") (pinfunction "PD1/PTCXY/OC4A/TXD0_31") (pintype "bidirectional"))
    )
    (net (code "51") (name "VCC") (class "Default")
      (node (ref "U2") (pin "6") (pinfunction "PE1/SCL1/T4/PTCXY_6") (pintype "bidirectional"))
    )
    (net (code "52") (name "unconnected-(J3-Pad14)") (class "Default")
      (node (ref "J3") (pin "14") (pinfunction "14_14") (pintype "passive"))
    )
    (net (code "53") (name "unconnected-(K2-NC-Pad4)") (class "Default")
      (node (ref "K2") (pin "4") (pinfunction "NC_4") (pintype "bidirectional"))
    )
  )
)
